# Main.net
KiCad netlist of a schematic drawn in Altium Designer
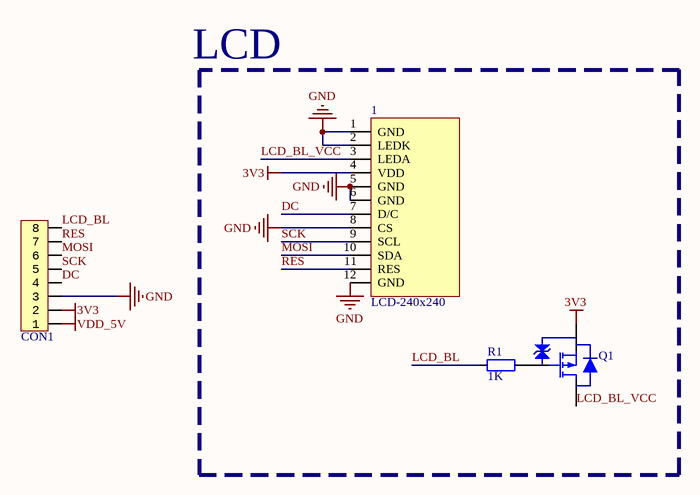
[diagram p0: Main.SchDoc]

(export (version "E")
  (design (tool "Eeschema 10.0.6"))
  (components
    (comp (ref "1")
      (value "LCD-240x240")
      (footprint "LCD-240x240-NoHole")
      (description "显示屏")
      (libsource (lib "mLib") (part "LCD-240x240"))
    )
    (comp (ref "CON1")
      (value "FFC_0.5_8")
      (footprint "FFC_0.5_8")
      (description "FFC")
      (libsource (lib "KitSprout") (part "FFC_0.5_8"))
    )
    (comp (ref "Q1")
      (value "AO3415A")
      (footprint "SOT23-3")
      (description "MOSFET")
      (fields (field (name "PUBLISHER") "Altium Limited"))
      (libsource (lib "MyPcbLib") (part "AO3415A"))
    )
    (comp (ref "R1")
      (value "1K")
      (footprint "RES_0402")
      (description "Resistor")
      (libsource (lib "MyPcbLib") (part "电阻-0402"))
    )
  )
  (nets
    (net (code "1") (name "/DC") (class "Default")
      (node (ref "1") (pin "7") (pinfunction "D/C_7") (pintype "passive"))
      (node (ref "CON1") (pin "4") (pinfunction "4_4") (pintype "passive"))
    )
    (net (code "2") (name "/LCD_BL") (class "Default")
      (node (ref "CON1") (pin "8") (pinfunction "8_8") (pintype "passive"))
      (node (ref "R1") (pin "1") (pinfunction "1_1") (pintype "passive"))
    )
    (net (code "3") (name "/LCD_BL_VCC") (class "Default")
      (node (ref "1") (pin "3") (pinfunction "LEDA_3") (pintype "passive"))
      (node (ref "Q1") (pin "3") (pinfunction "D_3") (pintype "passive"))
    )
    (net (code "4") (name "/MOSI") (class "Default")
      (node (ref "1") (pin "10") (pinfunction "SDA_10") (pintype "passive"))
      (node (ref "CON1") (pin "6") (pinfunction "6_6") (pintype "passive"))
    )
    (net (code "5") (name "/RES") (class "Default")
      (node (ref "1") (pin "11") (pinfunction "RES_11") (pintype "passive"))
      (node (ref "CON1") (pin "7") (pinfunction "7_7") (pintype "passive"))
    )
    (net (code "6") (name "/SCK") (class "Default")
      (node (ref "1") (pin "9") (pinfunction "SCL_9") (pintype "passive"))
      (node (ref "CON1") (pin "5") (pinfunction "5_5") (pintype "passive"))
    )
    (net (code "7") (name "3V3") (class "Default")
      (node (ref "1") (pin "4") (pinfunction "VDD_4") (pintype "passive"))
      (node (ref "CON1") (pin "2") (pinfunction "2_2") (pintype "passive"))
      (node (ref "Q1") (pin "2") (pinfunction "S_2") (pintype "passive"))
    )
    (net (code "8") (name "GND") (class "Default")
      (node (ref "1") (pin "1") (pinfunction "GND_1") (pintype "passive"))
      (node (ref "1") (pin "12") (pinfunction "GND_12") (pintype "passive"))
      (node (ref "1") (pin "2") (pinfunction "LEDK_2") (pintype "passive"))
      (node (ref "1") (pin "5") (pinfunction "GND_5") (pintype "passive"))
      (node (ref "1") (pin "6") (pinfunction "GND_6") (pintype "passive"))
      (node (ref "1") (pin "8") (pinfunction "CS_8") (pintype "passive"))
      (node (ref "CON1") (pin "3") (pinfunction "3_3") (pintype "passive"))
    )
    (net (code "9") (name "Net-(Q1-G)") (class "Default")
      (node (ref "Q1") (pin "1") (pinfunction "G_1") (pintype "passive"))
      (node (ref "R1") (pin "2") (pinfunction "2_2") (pintype "passive"))
    )
    (net (code "10") (name "VDD_5V") (class "Default")
      (node (ref "CON1") (pin "1") (pinfunction "1_1") (pintype "passive"))
    )
  )
)
